# shield.net
KiCad netlist of a schematic drawn in EAGLE
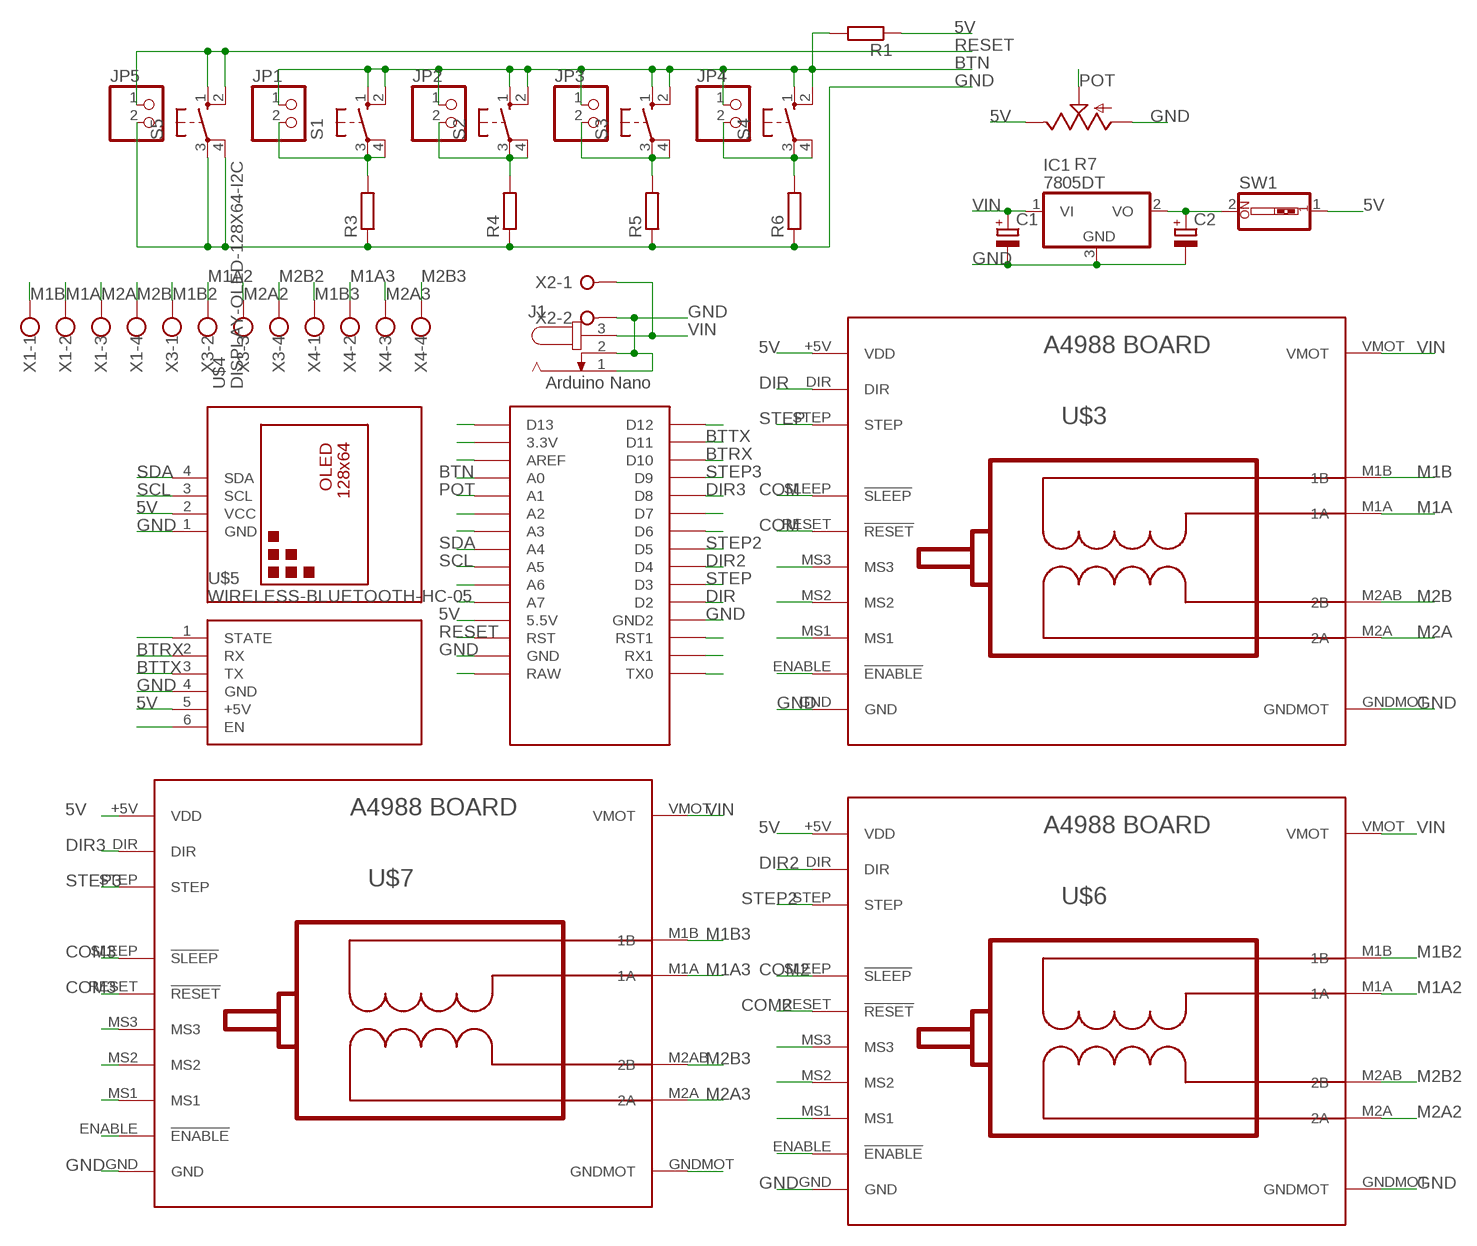
[diagram p0: schematic, sheet 1]

(export (version "E")
  (design (tool "Eeschema 10.0.6"))
  (components
    (comp (ref "C1")
      (value "CPOL-EUE2.5-7")
      (footprint "eagle-import:E2,5-7")
      (libsource (lib "eagle-import") (part "CPOL-EUE2.5-7"))
    )
    (comp (ref "C2")
      (value "CPOL-EUE2.5-7")
      (footprint "eagle-import:E2,5-7")
      (libsource (lib "eagle-import") (part "CPOL-EUE2.5-7"))
    )
    (comp (ref "IC1")
      (value "7805DT")
      (footprint "eagle-import:TO252")
      (libsource (lib "eagle-import") (part "78DT05"))
    )
    (comp (ref "J1")
      (value "JACK-PLUG1")
      (footprint "eagle-import:SPC4078")
      (libsource (lib "eagle-import") (part "JACK-PLUG1"))
    )
    (comp (ref "JP1")
      (value "PINHD-1X2")
      (footprint "eagle-import:1X02")
      (libsource (lib "eagle-import") (part "PINHD-1X2"))
    )
    (comp (ref "JP2")
      (value "PINHD-1X2")
      (footprint "eagle-import:1X02")
      (libsource (lib "eagle-import") (part "PINHD-1X2"))
    )
    (comp (ref "JP3")
      (value "PINHD-1X2")
      (footprint "eagle-import:1X02")
      (libsource (lib "eagle-import") (part "PINHD-1X2"))
    )
    (comp (ref "JP4")
      (value "PINHD-1X2")
      (footprint "eagle-import:1X02")
      (libsource (lib "eagle-import") (part "PINHD-1X2"))
    )
    (comp (ref "JP5")
      (value "PINHD-1X2")
      (footprint "eagle-import:1X02")
      (libsource (lib "eagle-import") (part "PINHD-1X2"))
    )
    (comp (ref "R1")
      (value "R-EU_R1206")
      (footprint "eagle-import:R1206")
      (libsource (lib "eagle-import") (part "R-EU_R1206"))
    )
    (comp (ref "R3")
      (value "R-EU_R1206")
      (footprint "eagle-import:R1206")
      (libsource (lib "eagle-import") (part "R-EU_R1206"))
    )
    (comp (ref "R4")
      (value "R-EU_R1206")
      (footprint "eagle-import:R1206")
      (libsource (lib "eagle-import") (part "R-EU_R1206"))
    )
    (comp (ref "R5")
      (value "R-EU_R1206")
      (footprint "eagle-import:R1206")
      (libsource (lib "eagle-import") (part "R-EU_R1206"))
    )
    (comp (ref "R6")
      (value "R-EU_R1206")
      (footprint "eagle-import:R1206")
      (libsource (lib "eagle-import") (part "R-EU_R1206"))
    )
    (comp (ref "R7")
      (value "TRIM_US-S63S")
      (footprint "eagle-import:S63S")
      (libsource (lib "eagle-import") (part "TRIM_US-S63S"))
    )
    (comp (ref "S1")
      (value "40-XX")
      (footprint "eagle-import:B3F-40XX")
      (fields (field (name "MF") "OMRON COMPONENTS USA") (field (name "MPN") "B3F-4000"))
      (libsource (lib "eagle-import") (part "40-XX"))
    )
    (comp (ref "S2")
      (value "40-XX")
      (footprint "eagle-import:B3F-40XX")
      (fields (field (name "MF") "OMRON COMPONENTS USA") (field (name "MPN") "B3F-4000"))
      (libsource (lib "eagle-import") (part "40-XX"))
    )
    (comp (ref "S3")
      (value "40-XX")
      (footprint "eagle-import:B3F-40XX")
      (fields (field (name "MF") "OMRON COMPONENTS USA") (field (name "MPN") "B3F-4000"))
      (libsource (lib "eagle-import") (part "40-XX"))
    )
    (comp (ref "S4")
      (value "40-XX")
      (footprint "eagle-import:B3F-40XX")
      (fields (field (name "MF") "OMRON COMPONENTS USA") (field (name "MPN") "B3F-4000"))
      (libsource (lib "eagle-import") (part "40-XX"))
    )
    (comp (ref "S5")
      (value "10-XX")
      (footprint "eagle-import:B3F-10XX")
      (fields (field (name "MPN") "B3F-1000"))
      (libsource (lib "eagle-import") (part "10-XX"))
    )
    (comp (ref "SW1")
      (value "SW_DIP-1")
      (footprint "eagle-import:EDG-01")
      (libsource (lib "eagle-import") (part "SW_DIP-1"))
    )
    (comp (ref "U$1")
      (value "NANO")
      (footprint "eagle-import:NANO")
      (libsource (lib "eagle-import") (part "NANO"))
    )
    (comp (ref "U$3")
      (value "BOARD_A4988")
      (footprint "eagle-import:BOARD_A4988")
      (libsource (lib "eagle-import") (part "BOARD_A4988"))
    )
    (comp (ref "U$4")
      (value "DISPLAY-OLED-128X64-I2C")
      (footprint "eagle-import:DISPLAY-OLED-128X64-I2C")
      (libsource (lib "eagle-import") (part "DISPLAY-OLED-128X64-I2C"))
    )
    (comp (ref "U$5")
      (value "WIRELESS-BLUETOOTH-HC-05")
      (footprint "eagle-import:WIRELESS-BLUETOOTH-HC-05")
      (libsource (lib "eagle-import") (part "WIRELESS-BLUETOOTH-HC-05"))
    )
    (comp (ref "U$6")
      (value "BOARD_A4988")
      (footprint "eagle-import:BOARD_A4988")
      (libsource (lib "eagle-import") (part "BOARD_A4988"))
    )
    (comp (ref "U$7")
      (value "BOARD_A4988")
      (footprint "eagle-import:BOARD_A4988")
      (libsource (lib "eagle-import") (part "BOARD_A4988"))
    )
    (comp (ref "X1")
      (value "W237-4")
      (footprint "eagle-import:W237-4")
      (libsource (lib "eagle-import") (part "W237-4"))
    )
    (comp (ref "X2")
      (value "W237-02P")
      (footprint "eagle-import:W237-132")
      (libsource (lib "eagle-import") (part "W237-02P"))
    )
    (comp (ref "X3")
      (value "W237-4")
      (footprint "eagle-import:W237-4")
      (libsource (lib "eagle-import") (part "W237-4"))
    )
    (comp (ref "X4")
      (value "W237-4")
      (footprint "eagle-import:W237-4")
      (libsource (lib "eagle-import") (part "W237-4"))
    )
  )
  (nets
    (net (code "1") (name "/5V") (class "Default")
      (node (ref "R1") (pin "1") (pinfunction "1_1") (pintype "passive"))
      (node (ref "R7") (pin "E") (pinfunction "E_E") (pintype "passive"))
      (node (ref "SW1") (pin "1") (pinfunction "1_1") (pintype "passive"))
      (node (ref "U$1") (pin "5V") (pinfunction "5.5V_5V") (pintype "bidirectional"))
      (node (ref "U$3") (pin "+5V") (pinfunction "VDD_+5V") (pintype "power_in"))
      (node (ref "U$4") (pin "2") (pinfunction "VCC_2") (pintype "power_in"))
      (node (ref "U$5") (pin "5") (pinfunction "+5V_5") (pintype "power_in"))
      (node (ref "U$6") (pin "+5V") (pinfunction "VDD_+5V") (pintype "power_in"))
      (node (ref "U$7") (pin "+5V") (pinfunction "VDD_+5V") (pintype "power_in"))
    )
    (net (code "2") (name "/BTN") (class "Default")
      (node (ref "JP1") (pin "1") (pinfunction "1_1") (pintype "passive"))
      (node (ref "JP2") (pin "1") (pinfunction "1_1") (pintype "passive"))
      (node (ref "JP3") (pin "1") (pinfunction "1_1") (pintype "passive"))
      (node (ref "JP4") (pin "1") (pinfunction "1_1") (pintype "passive"))
      (node (ref "R1") (pin "2") (pinfunction "2_2") (pintype "passive"))
      (node (ref "S1") (pin "1") (pinfunction "S_1") (pintype "passive"))
      (node (ref "S1") (pin "2") (pinfunction "S1_2") (pintype "passive"))
      (node (ref "S2") (pin "1") (pinfunction "S_1") (pintype "passive"))
      (node (ref "S2") (pin "2") (pinfunction "S1_2") (pintype "passive"))
      (node (ref "S3") (pin "1") (pinfunction "S_1") (pintype "passive"))
      (node (ref "S3") (pin "2") (pinfunction "S1_2") (pintype "passive"))
      (node (ref "S4") (pin "1") (pinfunction "S_1") (pintype "passive"))
      (node (ref "S4") (pin "2") (pinfunction "S1_2") (pintype "passive"))
      (node (ref "U$1") (pin "A0") (pinfunction "A0_A0") (pintype "bidirectional"))
    )
    (net (code "3") (name "/BTRX") (class "Default")
      (node (ref "U$1") (pin "D10") (pinfunction "D10_D10") (pintype "bidirectional"))
      (node (ref "U$5") (pin "2") (pinfunction "RX_2") (pintype "bidirectional"))
    )
    (net (code "4") (name "/BTTX") (class "Default")
      (node (ref "U$1") (pin "D11") (pinfunction "D11_D11") (pintype "bidirectional"))
      (node (ref "U$5") (pin "3") (pinfunction "TX_3") (pintype "bidirectional"))
    )
    (net (code "5") (name "/COM") (class "Default")
      (node (ref "U$3") (pin "RESET") (pinfunction "~{RESET}_RESET") (pintype "input"))
      (node (ref "U$3") (pin "SLEEP") (pinfunction "~{SLEEP}_SLEEP") (pintype "input"))
    )
    (net (code "6") (name "/COM2") (class "Default")
      (node (ref "U$6") (pin "RESET") (pinfunction "~{RESET}_RESET") (pintype "input"))
      (node (ref "U$6") (pin "SLEEP") (pinfunction "~{SLEEP}_SLEEP") (pintype "input"))
    )
    (net (code "7") (name "/COM3") (class "Default")
      (node (ref "U$7") (pin "RESET") (pinfunction "~{RESET}_RESET") (pintype "input"))
      (node (ref "U$7") (pin "SLEEP") (pinfunction "~{SLEEP}_SLEEP") (pintype "input"))
    )
    (net (code "8") (name "/DIR") (class "Default")
      (node (ref "U$1") (pin "D2") (pinfunction "D2_D2") (pintype "bidirectional"))
      (node (ref "U$3") (pin "DIR") (pinfunction "DIR_DIR") (pintype "input"))
    )
    (net (code "9") (name "/DIR2") (class "Default")
      (node (ref "U$1") (pin "D4") (pinfunction "D4_D4") (pintype "bidirectional"))
      (node (ref "U$6") (pin "DIR") (pinfunction "DIR_DIR") (pintype "input"))
    )
    (net (code "10") (name "/DIR3") (class "Default")
      (node (ref "U$1") (pin "D8") (pinfunction "D8_D8") (pintype "bidirectional"))
      (node (ref "U$7") (pin "DIR") (pinfunction "DIR_DIR") (pintype "input"))
    )
    (net (code "11") (name "/GND") (class "Default")
      (node (ref "C1") (pin "-") (pinfunction "-_-") (pintype "passive"))
      (node (ref "C2") (pin "-") (pinfunction "-_-") (pintype "passive"))
      (node (ref "IC1") (pin "3") (pinfunction "GND_3") (pintype "passive"))
      (node (ref "J1") (pin "1") (pinfunction "1_1") (pintype "passive"))
      (node (ref "J1") (pin "2") (pinfunction "2_2") (pintype "passive"))
      (node (ref "JP5") (pin "2") (pinfunction "2_2") (pintype "passive"))
      (node (ref "R3") (pin "1") (pinfunction "1_1") (pintype "passive"))
      (node (ref "R4") (pin "1") (pinfunction "1_1") (pintype "passive"))
      (node (ref "R5") (pin "1") (pinfunction "1_1") (pintype "passive"))
      (node (ref "R6") (pin "1") (pinfunction "1_1") (pintype "passive"))
      (node (ref "R7") (pin "A") (pinfunction "A_A") (pintype "passive"))
      (node (ref "S5") (pin "3") (pinfunction "P_3") (pintype "passive"))
      (node (ref "S5") (pin "4") (pinfunction "P1_4") (pintype "passive"))
      (node (ref "U$1") (pin "GND") (pinfunction "GND_GND") (pintype "bidirectional"))
      (node (ref "U$1") (pin "GND1") (pinfunction "GND2_GND1") (pintype "bidirectional"))
      (node (ref "U$3") (pin "GND") (pinfunction "GND_GND") (pintype "power_in"))
      (node (ref "U$3") (pin "GNDMOT") (pinfunction "GNDMOT_GNDMOT") (pintype "power_in"))
      (node (ref "U$4") (pin "1") (pinfunction "GND_1") (pintype "power_in"))
      (node (ref "U$5") (pin "4") (pinfunction "GND_4") (pintype "power_in"))
      (node (ref "U$6") (pin "GND") (pinfunction "GND_GND") (pintype "power_in"))
      (node (ref "U$6") (pin "GNDMOT") (pinfunction "GNDMOT_GNDMOT") (pintype "power_in"))
      (node (ref "U$7") (pin "GND") (pinfunction "GND_GND") (pintype "power_in"))
      (node (ref "U$7") (pin "GNDMOT") (pinfunction "GNDMOT_GNDMOT") (pintype "power_in"))
      (node (ref "X2") (pin "2") (pinfunction "KL_2") (pintype "passive"))
    )
    (net (code "12") (name "/M1A") (class "Default")
      (node (ref "U$3") (pin "M1A") (pinfunction "1A_M1A") (pintype "output"))
      (node (ref "X1") (pin "2") (pinfunction "KL_2") (pintype "passive"))
    )
    (net (code "13") (name "/M1A2") (class "Default")
      (node (ref "U$6") (pin "M1A") (pinfunction "1A_M1A") (pintype "output"))
      (node (ref "X3") (pin "2") (pinfunction "KL_2") (pintype "passive"))
    )
    (net (code "14") (name "/M1A3") (class "Default")
      (node (ref "U$7") (pin "M1A") (pinfunction "1A_M1A") (pintype "output"))
      (node (ref "X4") (pin "2") (pinfunction "KL_2") (pintype "passive"))
    )
    (net (code "15") (name "/M1B") (class "Default")
      (node (ref "U$3") (pin "M1B") (pinfunction "1B_M1B") (pintype "output"))
      (node (ref "X1") (pin "1") (pinfunction "KL_1") (pintype "passive"))
    )
    (net (code "16") (name "/M1B2") (class "Default")
      (node (ref "U$6") (pin "M1B") (pinfunction "1B_M1B") (pintype "output"))
      (node (ref "X3") (pin "1") (pinfunction "KL_1") (pintype "passive"))
    )
    (net (code "17") (name "/M1B3") (class "Default")
      (node (ref "U$7") (pin "M1B") (pinfunction "1B_M1B") (pintype "output"))
      (node (ref "X4") (pin "1") (pinfunction "KL_1") (pintype "passive"))
    )
    (net (code "18") (name "/M2A") (class "Default")
      (node (ref "U$3") (pin "M2A") (pinfunction "2A_M2A") (pintype "output"))
      (node (ref "X1") (pin "3") (pinfunction "KL_3") (pintype "passive"))
    )
    (net (code "19") (name "/M2A2") (class "Default")
      (node (ref "U$6") (pin "M2A") (pinfunction "2A_M2A") (pintype "output"))
      (node (ref "X3") (pin "3") (pinfunction "KL_3") (pintype "passive"))
    )
    (net (code "20") (name "/M2A3") (class "Default")
      (node (ref "U$7") (pin "M2A") (pinfunction "2A_M2A") (pintype "output"))
      (node (ref "X4") (pin "3") (pinfunction "KL_3") (pintype "passive"))
    )
    (net (code "21") (name "/M2B") (class "Default")
      (node (ref "U$3") (pin "M2AB") (pinfunction "2B_M2AB") (pintype "output"))
      (node (ref "X1") (pin "4") (pinfunction "KL_4") (pintype "passive"))
    )
    (net (code "22") (name "/M2B2") (class "Default")
      (node (ref "U$6") (pin "M2AB") (pinfunction "2B_M2AB") (pintype "output"))
      (node (ref "X3") (pin "4") (pinfunction "KL_4") (pintype "passive"))
    )
    (net (code "23") (name "/M2B3") (class "Default")
      (node (ref "U$7") (pin "M2AB") (pinfunction "2B_M2AB") (pintype "output"))
      (node (ref "X4") (pin "4") (pinfunction "KL_4") (pintype "passive"))
    )
    (net (code "24") (name "/POT") (class "Default")
      (node (ref "R7") (pin "S") (pinfunction "S_S") (pintype "passive"))
      (node (ref "U$1") (pin "A1") (pinfunction "A1_A1") (pintype "bidirectional"))
    )
    (net (code "25") (name "/RESET") (class "Default")
      (node (ref "JP5") (pin "1") (pinfunction "1_1") (pintype "passive"))
      (node (ref "S5") (pin "1") (pinfunction "S_1") (pintype "passive"))
      (node (ref "S5") (pin "2") (pinfunction "S1_2") (pintype "passive"))
      (node (ref "U$1") (pin "RST") (pinfunction "RST_RST") (pintype "bidirectional"))
    )
    (net (code "26") (name "/SCL") (class "Default")
      (node (ref "U$1") (pin "A5") (pinfunction "A5_A5") (pintype "bidirectional"))
      (node (ref "U$4") (pin "3") (pinfunction "SCL_3") (pintype "bidirectional"))
    )
    (net (code "27") (name "/SDA") (class "Default")
      (node (ref "U$1") (pin "A4") (pinfunction "A4_A4") (pintype "bidirectional"))
      (node (ref "U$4") (pin "4") (pinfunction "SDA_4") (pintype "bidirectional"))
    )
    (net (code "28") (name "/STEP") (class "Default")
      (node (ref "U$1") (pin "D3") (pinfunction "D3_D3") (pintype "bidirectional"))
      (node (ref "U$3") (pin "STEP") (pinfunction "STEP_STEP") (pintype "input"))
    )
    (net (code "29") (name "/STEP2") (class "Default")
      (node (ref "U$1") (pin "D5") (pinfunction "D5_D5") (pintype "bidirectional"))
      (node (ref "U$6") (pin "STEP") (pinfunction "STEP_STEP") (pintype "input"))
    )
    (net (code "30") (name "/STEP3") (class "Default")
      (node (ref "U$1") (pin "D9") (pinfunction "D9_D9") (pintype "bidirectional"))
      (node (ref "U$7") (pin "STEP") (pinfunction "STEP_STEP") (pintype "input"))
    )
    (net (code "31") (name "/VIN") (class "Default")
      (node (ref "C1") (pin "+") (pinfunction "+_+") (pintype "passive"))
      (node (ref "IC1") (pin "1") (pinfunction "VI_1") (pintype "input"))
      (node (ref "J1") (pin "3") (pinfunction "3_3") (pintype "passive"))
      (node (ref "U$3") (pin "VMOT") (pinfunction "VMOT_VMOT") (pintype "power_in"))
      (node (ref "U$6") (pin "VMOT") (pinfunction "VMOT_VMOT") (pintype "power_in"))
      (node (ref "U$7") (pin "VMOT") (pinfunction "VMOT_VMOT") (pintype "power_in"))
      (node (ref "X2") (pin "1") (pinfunction "KL_1") (pintype "passive"))
    )
    (net (code "32") (name "Net-(IC1-VO)") (class "Default")
      (node (ref "C2") (pin "+") (pinfunction "+_+") (pintype "passive"))
      (node (ref "IC1") (pin "2") (pinfunction "VO_2") (pintype "passive"))
      (node (ref "SW1") (pin "2") (pinfunction "2_2") (pintype "passive"))
    )
    (net (code "33") (name "Net-(S1-P)") (class "Default")
      (node (ref "JP1") (pin "2") (pinfunction "2_2") (pintype "passive"))
      (node (ref "R3") (pin "2") (pinfunction "2_2") (pintype "passive"))
      (node (ref "S1") (pin "3") (pinfunction "P_3") (pintype "passive"))
      (node (ref "S1") (pin "4") (pinfunction "P1_4") (pintype "passive"))
    )
    (net (code "34") (name "Net-(S2-P)") (class "Default")
      (node (ref "JP2") (pin "2") (pinfunction "2_2") (pintype "passive"))
      (node (ref "R4") (pin "2") (pinfunction "2_2") (pintype "passive"))
      (node (ref "S2") (pin "3") (pinfunction "P_3") (pintype "passive"))
      (node (ref "S2") (pin "4") (pinfunction "P1_4") (pintype "passive"))
    )
    (net (code "35") (name "Net-(S3-P)") (class "Default")
      (node (ref "JP3") (pin "2") (pinfunction "2_2") (pintype "passive"))
      (node (ref "R5") (pin "2") (pinfunction "2_2") (pintype "passive"))
      (node (ref "S3") (pin "3") (pinfunction "P_3") (pintype "passive"))
      (node (ref "S3") (pin "4") (pinfunction "P1_4") (pintype "passive"))
    )
    (net (code "36") (name "Net-(S4-P)") (class "Default")
      (node (ref "JP4") (pin "2") (pinfunction "2_2") (pintype "passive"))
      (node (ref "R6") (pin "2") (pinfunction "2_2") (pintype "passive"))
      (node (ref "S4") (pin "3") (pinfunction "P_3") (pintype "passive"))
      (node (ref "S4") (pin "4") (pinfunction "P1_4") (pintype "passive"))
    )
    (net (code "37") (name "unconnected-(U$1-Pad3.3V)") (class "Default")
      (node (ref "U$1") (pin "3.3V") (pinfunction "3.3V_3.3V") (pintype "bidirectional"))
    )
    (net (code "38") (name "unconnected-(U$1-PadA2)") (class "Default")
      (node (ref "U$1") (pin "A2") (pinfunction "A2_A2") (pintype "bidirectional"))
    )
    (net (code "39") (name "unconnected-(U$1-PadA3)") (class "Default")
      (node (ref "U$1") (pin "A3") (pinfunction "A3_A3") (pintype "bidirectional"))
    )
    (net (code "40") (name "unconnected-(U$1-PadA6)") (class "Default")
      (node (ref "U$1") (pin "A6") (pinfunction "A6_A6") (pintype "bidirectional"))
    )
    (net (code "41") (name "unconnected-(U$1-PadA7)") (class "Default")
      (node (ref "U$1") (pin "A7") (pinfunction "A7_A7") (pintype "bidirectional"))
    )
    (net (code "42") (name "unconnected-(U$1-PadAREF)") (class "Default")
      (node (ref "U$1") (pin "AREF") (pinfunction "AREF_AREF") (pintype "bidirectional"))
    )
    (net (code "43") (name "unconnected-(U$1-PadD6)") (class "Default")
      (node (ref "U$1") (pin "D6") (pinfunction "D6_D6") (pintype "bidirectional"))
    )
    (net (code "44") (name "unconnected-(U$1-PadD7)") (class "Default")
      (node (ref "U$1") (pin "D7") (pinfunction "D7_D7") (pintype "bidirectional"))
    )
    (net (code "45") (name "unconnected-(U$1-PadD12)") (class "Default")
      (node (ref "U$1") (pin "D12") (pinfunction "D12_D12") (pintype "bidirectional"))
    )
    (net (code "46") (name "unconnected-(U$1-PadD13)") (class "Default")
      (node (ref "U$1") (pin "D13") (pinfunction "D13_D13") (pintype "bidirectional"))
    )
    (net (code "47") (name "unconnected-(U$1-PadICSP1)") (class "Default")
      (node (ref "U$1") (pin "ICSP1") (pinfunction "ICSP1_ICSP1") (pintype "bidirectional"))
    )
    (net (code "48") (name "unconnected-(U$1-PadICSP2)") (class "Default")
      (node (ref "U$1") (pin "ICSP2") (pinfunction "ICSP2_ICSP2") (pintype "bidirectional"))
    )
    (net (code "49") (name "unconnected-(U$1-PadICSP3)") (class "Default")
      (node (ref "U$1") (pin "ICSP3") (pinfunction "ICSP3_ICSP3") (pintype "bidirectional"))
    )
    (net (code "50") (name "unconnected-(U$1-PadICSP4)") (class "Default")
      (node (ref "U$1") (pin "ICSP4") (pinfunction "ICSP4_ICSP4") (pintype "bidirectional"))
    )
    (net (code "51") (name "unconnected-(U$1-PadICSP5)") (class "Default")
      (node (ref "U$1") (pin "ICSP5") (pinfunction "ICSP5_ICSP5") (pintype "bidirectional"))
    )
    (net (code "52") (name "unconnected-(U$1-PadICSP6)") (class "Default")
      (node (ref "U$1") (pin "ICSP6") (pinfunction "ICSP6_ICSP6") (pintype "bidirectional"))
    )
    (net (code "53") (name "unconnected-(U$1-PadRAW)") (class "Default")
      (node (ref "U$1") (pin "RAW") (pinfunction "RAW_RAW") (pintype "bidirectional"))
    )
    (net (code "54") (name "unconnected-(U$1-PadRST1)") (class "Default")
      (node (ref "U$1") (pin "RST1") (pinfunction "RST1_RST1") (pintype "bidirectional"))
    )
    (net (code "55") (name "unconnected-(U$1-PadRX1)") (class "Default")
      (node (ref "U$1") (pin "RX1") (pinfunction "RX1_RX1") (pintype "bidirectional"))
    )
    (net (code "56") (name "unconnected-(U$1-PadTX0)") (class "Default")
      (node (ref "U$1") (pin "TX0") (pinfunction "TX0_TX0") (pintype "bidirectional"))
    )
    (net (code "57") (name "unconnected-(U$3-PadMS1)") (class "Default")
      (node (ref "U$3") (pin "MS1") (pinfunction "MS1_MS1") (pintype "input"))
    )
    (net (code "58") (name "unconnected-(U$3-PadMS2)") (class "Default")
      (node (ref "U$3") (pin "MS2") (pinfunction "MS2_MS2") (pintype "input"))
    )
    (net (code "59") (name "unconnected-(U$3-PadMS3)") (class "Default")
      (node (ref "U$3") (pin "MS3") (pinfunction "MS3_MS3") (pintype "input"))
    )
    (net (code "60") (name "unconnected-(U$3-~{ENABLE}-PadENABLE)") (class "Default")
      (node (ref "U$3") (pin "ENABLE") (pinfunction "~{ENABLE}_ENABLE") (pintype "input"))
    )
    (net (code "61") (name "unconnected-(U$5-EN-Pad6)") (class "Default")
      (node (ref "U$5") (pin "6") (pinfunction "EN_6") (pintype "bidirectional"))
    )
    (net (code "62") (name "unconnected-(U$5-STATE-Pad1)") (class "Default")
      (node (ref "U$5") (pin "1") (pinfunction "STATE_1") (pintype "bidirectional"))
    )
    (net (code "63") (name "unconnected-(U$6-PadMS1)") (class "Default")
      (node (ref "U$6") (pin "MS1") (pinfunction "MS1_MS1") (pintype "input"))
    )
    (net (code "64") (name "unconnected-(U$6-PadMS2)") (class "Default")
      (node (ref "U$6") (pin "MS2") (pinfunction "MS2_MS2") (pintype "input"))
    )
    (net (code "65") (name "unconnected-(U$6-PadMS3)") (class "Default")
      (node (ref "U$6") (pin "MS3") (pinfunction "MS3_MS3") (pintype "input"))
    )
    (net (code "66") (name "unconnected-(U$6-~{ENABLE}-PadENABLE)") (class "Default")
      (node (ref "U$6") (pin "ENABLE") (pinfunction "~{ENABLE}_ENABLE") (pintype "input"))
    )
    (net (code "67") (name "unconnected-(U$7-PadMS1)") (class "Default")
      (node (ref "U$7") (pin "MS1") (pinfunction "MS1_MS1") (pintype "input"))
    )
    (net (code "68") (name "unconnected-(U$7-PadMS2)") (class "Default")
      (node (ref "U$7") (pin "MS2") (pinfunction "MS2_MS2") (pintype "input"))
    )
    (net (code "69") (name "unconnected-(U$7-PadMS3)") (class "Default")
      (node (ref "U$7") (pin "MS3") (pinfunction "MS3_MS3") (pintype "input"))
    )
    (net (code "70") (name "unconnected-(U$7-~{ENABLE}-PadENABLE)") (class "Default")
      (node (ref "U$7") (pin "ENABLE") (pinfunction "~{ENABLE}_ENABLE") (pintype "input"))
    )
  )
)
